# top.net
KiCad netlist of a schematic drawn in Altium Designer
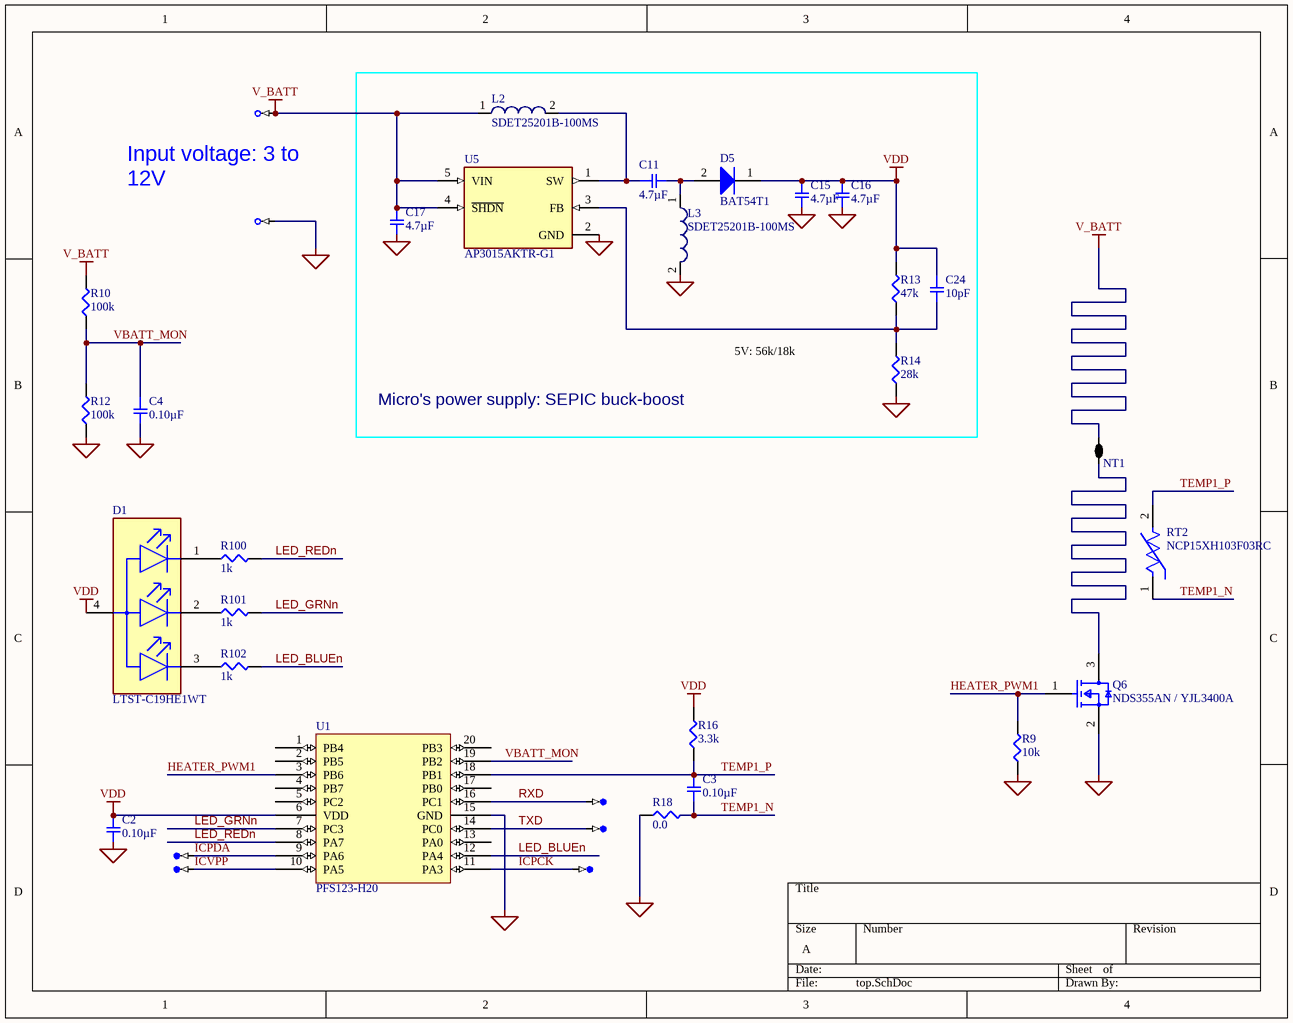
[diagram p0: top.SchDoc]

(export (version "E")
  (design (tool "Eeschema 10.0.6"))
  (components
    (comp (ref "1")
      (value "TP-TH-C-152-H90")
      (footprint "TP-TH-C-152-H90")
      (description "Test Point, Through Hole, Hole Size 0.9 mm, PCB Mount with Silkscreen Box")
      (libsource (lib "TP-TH-C-152-H90-") (part "TP-TH-C-152-H90"))
    )
    (comp (ref "2")
      (value "TP-TH-C-152-H90")
      (footprint "TP-TH-C-152-H90")
      (description "Test Point, Through Hole, Hole Size 0.9 mm, PCB Mount with Silkscreen Box")
      (libsource (lib "TP-TH-C-152-H90-") (part "TP-TH-C-152-H90"))
    )
    (comp (ref "C2")
      (value "0.10µF")
      (footprint "SMD-0402C")
      (description "CAP CER 0.1UF 10V X5R 0402")
      (fields
        (field (name "DIGI-KEY PART NUMBER") "490-10008-1-ND")
        (field (name "PART NUMBER") "GRM152R61A104KE19D")
      )
      (libsource (lib "capacitor_murata_0402") (part "GRM152R61A104KE19D"))
    )
    (comp (ref "C3")
      (value "0.10µF")
      (footprint "SMD-0402C")
      (description "CAP CER 0.1UF 10V X5R 0402")
      (fields
        (field (name "DIGI-KEY PART NUMBER") "490-10008-1-ND")
        (field (name "PART NUMBER") "GRM152R61A104KE19D")
      )
      (libsource (lib "capacitor_murata_0402") (part "GRM152R61A104KE19D"))
    )
    (comp (ref "C4")
      (value "0.10µF")
      (footprint "SMD-0402C")
      (description "CAP CER 0.1UF 10V X5R 0402")
      (fields
        (field (name "DIGI-KEY PART NUMBER") "490-10008-1-ND")
        (field (name "PART NUMBER") "GRM152R61A104KE19D")
      )
      (libsource (lib "capacitor_murata_0402") (part "GRM152R61A104KE19D"))
    )
    (comp (ref "C11")
      (value "4.7µF")
      (footprint "SMD-0603C")
      (description "CAP CER 4.7UF 10V X6S 0603")
      (fields
        (field (name "DIGI-KEY PART NUMBER") "490-10464-1-ND")
        (field (name "PART NUMBER") "GRM185C81A475KE11D")
      )
      (libsource (lib "capacitor_murata_0603") (part "GRM185C81A475KE11D"))
    )
    (comp (ref "C15")
      (value "4.7µF")
      (footprint "SMD-0603C")
      (description "CAP CER 4.7UF 10V X6S 0603")
      (fields
        (field (name "DIGI-KEY PART NUMBER") "490-10464-1-ND")
        (field (name "PART NUMBER") "GRM185C81A475KE11D")
      )
      (libsource (lib "capacitor_murata_0603") (part "GRM185C81A475KE11D"))
    )
    (comp (ref "C16")
      (value "4.7µF")
      (footprint "SMD-0603C")
      (description "CAP CER 4.7UF 10V X6S 0603")
      (fields
        (field (name "DIGI-KEY PART NUMBER") "490-10464-1-ND")
        (field (name "PART NUMBER") "GRM185C81A475KE11D")
      )
      (libsource (lib "capacitor_murata_0603") (part "GRM185C81A475KE11D"))
    )
    (comp (ref "C17")
      (value "4.7µF")
      (footprint "SMD-0603C")
      (description "CAP CER 4.7UF 10V X6S 0603")
      (fields
        (field (name "DIGI-KEY PART NUMBER") "490-10464-1-ND")
        (field (name "PART NUMBER") "GRM185C81A475KE11D")
      )
      (libsource (lib "capacitor_murata_0603") (part "GRM185C81A475KE11D"))
    )
    (comp (ref "C24")
      (value "10pF")
      (footprint "SMD-0402C")
      (description "CAP CER 10PF 50V NP0 0402")
      (fields
        (field (name "DIGI-KEY PART NUMBER") "490-10668-1-ND")
        (field (name "PART NUMBER") "GCM1555C1H100JA16D")
      )
      (libsource (lib "capacitor_murata_0402") (part "GCM1555C1H100JA16D"))
    )
    (comp (ref "D1")
      (value "LTST-C19HE1WT")
      (footprint "FP-LTST-C19HE1WT-MFG")
      (description "LED RGB DIFFUSED CHIP SMD")
      (libsource (lib "Altium Content Vault") (part "2c4e1fdd461916b293eda504ca5a2b6"))
    )
    (comp (ref "D5")
      (value "BAT54T1")
      (footprint "ONSC-SOD-123-2-425-04_V")
      (description "Schottky Barrier Diode, 2-Pin SOD-123, Tape and Reel")
      (fields (field (name "MANUFACTURER") "On Semiconductor"))
      (libsource (lib "Altium Content Vault") (part "ONSC-D-K1A2-2"))
    )
    (comp (ref "L2")
      (value "SDET25201B-100MS")
      (footprint "WE-LQS 252012")
      (description "FIXED IND 10UH 900MA 408MOHM SMD")
      (fields (field (name "MANUFACTURER") "Wuerth Elektronik") (field (name "PARTNUMBER") "74404024100"))
      (libsource (lib "Altium Content Vault") (part "WE-IND-INDUCTOR-2"))
    )
    (comp (ref "L3")
      (value "SDET25201B-100MS")
      (footprint "WE-LQS 252012")
      (description "FIXED IND 10UH 900MA 408MOHM SMD")
      (fields (field (name "MANUFACTURER") "Wuerth Elektronik") (field (name "PARTNUMBER") "74404024100"))
      (libsource (lib "Altium Content Vault") (part "WE-IND-INDUCTOR-2"))
    )
    (comp (ref "NT1")
      (value "2 way net tie junction")
      (footprint "2way_LP")
      (libsource (lib "NetTie") (part "2way"))
    )
    (comp (ref "Q6")
      (value "NDS355AN / YJL3400A")
      (footprint "FP-527AG-01-IPC_C")
      (description "MOSFET N-CH 30V 1.7A SSOT3")
      (fields
        (field (name "OCTOPART") "https://octopart.com/nds355an-on+semiconductor-84330922")
        (field (name "MANUFACTURER PART NUMBER") "NDS355AN")
      )
      (libsource (lib "Altium Content Vault") (part "3b9c635fedb024a5347a57b145af9cc"))
    )
    (comp (ref "R9")
      (value "10k")
      (footprint "SMD-0402-RES")
      (description "RES SMD 10K OHM 5% 1/10W 0402")
      (fields (field (name "PART NUMBER") "ERJ-2GEJ103X") (field (name "DIGI-KEY PART NUMBER") "P10KJCT-ND"))
      (libsource (lib "Panasonic_ERJ_0402") (part "ERJ-2GEJ103X"))
    )
    (comp (ref "R10")
      (value "100k")
      (footprint "SMD-0402-RES")
      (description "RES SMD 100K OHM 5% 1/10W 0402")
      (fields (field (name "PART NUMBER") "ERJ-2GEJ104X") (field (name "DIGI-KEY PART NUMBER") "P100KJCT-ND"))
      (libsource (lib "Panasonic_ERJ_0402") (part "ERJ-2GEJ104X"))
    )
    (comp (ref "R12")
      (value "100k")
      (footprint "SMD-0402-RES")
      (description "RES SMD 100K OHM 5% 1/10W 0402")
      (fields (field (name "PART NUMBER") "ERJ-2GEJ104X") (field (name "DIGI-KEY PART NUMBER") "P100KJCT-ND"))
      (libsource (lib "Panasonic_ERJ_0402") (part "ERJ-2GEJ104X"))
    )
    (comp (ref "R13")
      (value "47k")
      (footprint "SMD-0402-RES")
      (description "RES SMD 10K OHM 5% 1/10W 0402")
      (fields (field (name "PART NUMBER") "ERJ-2GEJ103X") (field (name "DIGI-KEY PART NUMBER") "P10KJCT-ND"))
      (libsource (lib "Panasonic_ERJ_0402") (part "ERJ-2GEJ103X"))
    )
    (comp (ref "R14")
      (value "28k")
      (footprint "SMD-0402-RES")
      (description "RES SMD 10K OHM 5% 1/10W 0402")
      (fields (field (name "PART NUMBER") "ERJ-2GEJ103X") (field (name "DIGI-KEY PART NUMBER") "P10KJCT-ND"))
      (libsource (lib "Panasonic_ERJ_0402") (part "ERJ-2GEJ103X"))
    )
    (comp (ref "R16")
      (value "3.3k")
      (footprint "SMD-0402-RES")
      (description "RES SMD 3.3K OHM 5% 1/10W 0402")
      (fields (field (name "PART NUMBER") "ERJ-2GEJ332X") (field (name "DIGI-KEY PART NUMBER") "P3.3KJCT-ND"))
      (libsource (lib "Panasonic_ERJ_0402") (part "ERJ-2GEJ332X"))
    )
    (comp (ref "R18")
      (value "0.0")
      (footprint "SMD-0402-RES")
      (description "RES SMD 0.0OHM JUMPER 1/10W 0402")
      (fields (field (name "PART NUMBER") "ERJ-2GE0R00X") (field (name "DIGI-KEY PART NUMBER") "P0.0JCT-ND"))
      (libsource (lib "Panasonic_ERJ_0402") (part "ERJ-2GE0R00X"))
    )
    (comp (ref "R100")
      (value "1k")
      (footprint "SMD-0402-RES")
      (description "RES SMD 1K OHM 5% 1/10W 0402")
      (fields (field (name "PART NUMBER") "ERJ-2GEJ102X") (field (name "DIGI-KEY PART NUMBER") "P1.0KJCT-ND"))
      (libsource (lib "Panasonic_ERJ_0402") (part "ERJ-2GEJ102X"))
    )
    (comp (ref "R101")
      (value "1k")
      (footprint "SMD-0402-RES")
      (description "RES SMD 1K OHM 5% 1/10W 0402")
      (fields (field (name "PART NUMBER") "ERJ-2GEJ102X") (field (name "DIGI-KEY PART NUMBER") "P1.0KJCT-ND"))
      (libsource (lib "Panasonic_ERJ_0402") (part "ERJ-2GEJ102X"))
    )
    (comp (ref "R102")
      (value "1k")
      (footprint "SMD-0402-RES")
      (description "RES SMD 1K OHM 5% 1/10W 0402")
      (fields (field (name "PART NUMBER") "ERJ-2GEJ102X") (field (name "DIGI-KEY PART NUMBER") "P1.0KJCT-ND"))
      (libsource (lib "Panasonic_ERJ_0402") (part "ERJ-2GEJ102X"))
    )
    (comp (ref "RT2")
      (value "NCP15XH103F03RC")
      (footprint "FP-NCP15-NCU15-0_05-IPC_C")
      (description "NTC Thermistor for Temperature Sensor, 0402, 10kΩ, 1%, 0.1mA, 5V")
      (fields (field (name "TOLERANCE") "1%"))
      (libsource (lib "Altium Content Vault") (part "3b148a6ebabc5fb4d708a66c052d352"))
    )
    (comp (ref "TP1")
      (value "TP-SM-C-100")
      (footprint "TP-SM-C-100")
      (description "Test Point, Surface Mount, Circular, Pad Diameter 1 mm")
      (fields (field (name "MANUFACTURER") "No Vendor"))
      (libsource (lib "TP-SM-C-100") (part "CMP-0484-00002-2"))
    )
    (comp (ref "TP2")
      (value "TP-SM-C-100")
      (footprint "TP-SM-C-100")
      (description "Test Point, Surface Mount, Circular, Pad Diameter 1 mm")
      (fields (field (name "MANUFACTURER") "No Vendor"))
      (libsource (lib "TP-SM-C-100") (part "CMP-0484-00002-2"))
    )
    (comp (ref "TP3")
      (value "TP-SM-C-100")
      (footprint "TP-SM-C-100")
      (description "Test Point, Surface Mount, Circular, Pad Diameter 1 mm")
      (fields (field (name "MANUFACTURER") "No Vendor"))
      (libsource (lib "TP-SM-C-100") (part "CMP-0484-00002-2"))
    )
    (comp (ref "TP4")
      (value "TP-SM-C-100")
      (footprint "TP-SM-C-100")
      (description "Test Point, Surface Mount, Circular, Pad Diameter 1 mm")
      (fields (field (name "MANUFACTURER") "No Vendor"))
      (libsource (lib "TP-SM-C-100") (part "CMP-0484-00002-2"))
    )
    (comp (ref "TP5")
      (value "TP-SM-C-100")
      (footprint "TP-SM-C-100")
      (description "Test Point, Surface Mount, Circular, Pad Diameter 1 mm")
      (fields (field (name "MANUFACTURER") "No Vendor"))
      (libsource (lib "TP-SM-C-100") (part "CMP-0484-00002-2"))
    )
    (comp (ref "U1")
      (value "PFS123-H20")
      (footprint "TSOP100P600X135-20N")
      (libsource (lib "PFS123") (part "PFS123-H20"))
    )
    (comp (ref "U5")
      (value "AP3015AKTR-G1")
      (footprint "SOT95P280X145-5N")
      (description "Boost Switching Regulator IC Positive Adjustable 1.23V 1 Output 75mA (Switch) SC-74A, SOT-753")
      (fields (field (name "MF") "Diodes Inc."))
      (libsource (lib "AP3015AKTR-G1") (part "AP3015AKTR-G1"))
    )
  )
  (nets
    (net (code "1") (name "/HEATER_PWM1") (class "Default")
      (node (ref "Q6") (pin "1") (pinfunction "G_1") (pintype "passive"))
      (node (ref "R9") (pin "2") (pinfunction "2_2") (pintype "passive"))
      (node (ref "U1") (pin "3") (pinfunction "PB6_3") (pintype "bidirectional"))
    )
    (net (code "2") (name "/ICPCK") (class "Default")
      (node (ref "TP3") (pin "1") (pinfunction "1_1") (pintype "input"))
      (node (ref "U1") (pin "11") (pinfunction "PA3_11") (pintype "bidirectional"))
    )
    (net (code "3") (name "/ICPDA") (class "Default")
      (node (ref "TP1") (pin "1") (pinfunction "1_1") (pintype "input"))
      (node (ref "U1") (pin "9") (pinfunction "PA6_9") (pintype "bidirectional"))
    )
    (net (code "4") (name "/ICVPP") (class "Default")
      (node (ref "TP2") (pin "1") (pinfunction "1_1") (pintype "input"))
      (node (ref "U1") (pin "10") (pinfunction "PA5_10") (pintype "bidirectional"))
    )
    (net (code "5") (name "/LED_BLUEn") (class "Default")
      (node (ref "R102") (pin "2") (pinfunction "2_2") (pintype "passive"))
      (node (ref "U1") (pin "12") (pinfunction "PA4_12") (pintype "bidirectional"))
    )
    (net (code "6") (name "/LED_GRNn") (class "Default")
      (node (ref "R101") (pin "2") (pinfunction "2_2") (pintype "passive"))
      (node (ref "U1") (pin "7") (pinfunction "PC3_7") (pintype "bidirectional"))
    )
    (net (code "7") (name "/LED_REDn") (class "Default")
      (node (ref "R100") (pin "2") (pinfunction "2_2") (pintype "passive"))
      (node (ref "U1") (pin "8") (pinfunction "PA7_8") (pintype "bidirectional"))
    )
    (net (code "8") (name "/RXD") (class "Default")
      (node (ref "TP4") (pin "1") (pinfunction "1_1") (pintype "input"))
      (node (ref "U1") (pin "16") (pinfunction "PC1_16") (pintype "bidirectional"))
    )
    (net (code "9") (name "/TEMP1_N") (class "Default")
      (node (ref "C3") (pin "2") (pinfunction "2_2") (pintype "passive"))
      (node (ref "R18") (pin "2") (pinfunction "2_2") (pintype "passive"))
      (node (ref "RT2") (pin "1") (pinfunction "1_1") (pintype "passive"))
    )
    (net (code "10") (name "/TEMP1_P") (class "Default")
      (node (ref "C3") (pin "1") (pinfunction "1_1") (pintype "passive"))
      (node (ref "R16") (pin "1") (pinfunction "1_1") (pintype "passive"))
      (node (ref "RT2") (pin "2") (pinfunction "2_2") (pintype "passive"))
      (node (ref "U1") (pin "18") (pinfunction "PB1_18") (pintype "bidirectional"))
    )
    (net (code "11") (name "/TXD") (class "Default")
      (node (ref "TP5") (pin "1") (pinfunction "1_1") (pintype "input"))
      (node (ref "U1") (pin "14") (pinfunction "PC0_14") (pintype "bidirectional"))
    )
    (net (code "12") (name "/VBATT_MON") (class "Default")
      (node (ref "C4") (pin "1") (pinfunction "1_1") (pintype "passive"))
      (node (ref "R10") (pin "1") (pinfunction "1_1") (pintype "passive"))
      (node (ref "R12") (pin "2") (pinfunction "2_2") (pintype "passive"))
      (node (ref "U1") (pin "19") (pinfunction "PB2_19") (pintype "bidirectional"))
    )
    (net (code "13") (name "GND") (class "Default")
      (node (ref "2") (pin "1") (pinfunction "1_1") (pintype "input"))
      (node (ref "C15") (pin "2") (pinfunction "2_2") (pintype "passive"))
      (node (ref "C16") (pin "2") (pinfunction "2_2") (pintype "passive"))
      (node (ref "C17") (pin "2") (pinfunction "2_2") (pintype "passive"))
      (node (ref "C2") (pin "2") (pinfunction "2_2") (pintype "passive"))
      (node (ref "C4") (pin "2") (pinfunction "2_2") (pintype "passive"))
      (node (ref "L3") (pin "2") (pinfunction "2_2") (pintype "passive"))
      (node (ref "Q6") (pin "2") (pinfunction "S_2") (pintype "passive"))
      (node (ref "R12") (pin "1") (pinfunction "1_1") (pintype "passive"))
      (node (ref "R14") (pin "1") (pinfunction "1_1") (pintype "passive"))
      (node (ref "R18") (pin "1") (pinfunction "1_1") (pintype "passive"))
      (node (ref "R9") (pin "1") (pinfunction "1_1") (pintype "passive"))
      (node (ref "U1") (pin "15") (pinfunction "GND_15") (pintype "power_in"))
      (node (ref "U5") (pin "2") (pinfunction "GND_2") (pintype "power_in"))
    )
    (net (code "14") (name "Net-(D1-BLUE_C)") (class "Default")
      (node (ref "D1") (pin "3") (pinfunction "BLUE_C_3") (pintype "passive"))
      (node (ref "R102") (pin "1") (pinfunction "1_1") (pintype "passive"))
    )
    (net (code "15") (name "Net-(D1-GREEN_C)") (class "Default")
      (node (ref "D1") (pin "2") (pinfunction "GREEN_C_2") (pintype "passive"))
      (node (ref "R101") (pin "1") (pinfunction "1_1") (pintype "passive"))
    )
    (net (code "16") (name "Net-(D1-RED_C)") (class "Default")
      (node (ref "D1") (pin "1") (pinfunction "RED_C_1") (pintype "passive"))
      (node (ref "R100") (pin "1") (pinfunction "1_1") (pintype "passive"))
    )
    (net (code "17") (name "Net-(D5-A)") (class "Default")
      (node (ref "C11") (pin "2") (pinfunction "2_2") (pintype "passive"))
      (node (ref "D5") (pin "2") (pinfunction "A_2") (pintype "passive"))
      (node (ref "L3") (pin "1") (pinfunction "1_1") (pintype "passive"))
    )
    (net (code "18") (name "Net-(Q6-D)") (class "Default")
      (node (ref "NT1") (pin "2") (pinfunction "2_2") (pintype "passive"))
      (node (ref "Q6") (pin "3") (pinfunction "D_3") (pintype "passive"))
    )
    (net (code "19") (name "Net-(U5-FB)") (class "Default")
      (node (ref "C24") (pin "2") (pinfunction "2_2") (pintype "passive"))
      (node (ref "R13") (pin "1") (pinfunction "1_1") (pintype "passive"))
      (node (ref "R14") (pin "2") (pinfunction "2_2") (pintype "passive"))
      (node (ref "U5") (pin "3") (pinfunction "FB_3") (pintype "input"))
    )
    (net (code "20") (name "Net-(U5-SW)") (class "Default")
      (node (ref "C11") (pin "1") (pinfunction "1_1") (pintype "passive"))
      (node (ref "L2") (pin "2") (pinfunction "2_2") (pintype "passive"))
      (node (ref "U5") (pin "1") (pinfunction "SW_1") (pintype "output"))
    )
    (net (code "21") (name "VDD") (class "Default")
      (node (ref "C15") (pin "1") (pinfunction "1_1") (pintype "passive"))
      (node (ref "C16") (pin "1") (pinfunction "1_1") (pintype "passive"))
      (node (ref "C2") (pin "1") (pinfunction "1_1") (pintype "passive"))
      (node (ref "C24") (pin "1") (pinfunction "1_1") (pintype "passive"))
      (node (ref "D1") (pin "4") (pinfunction "A_4") (pintype "passive"))
      (node (ref "D5") (pin "1") (pinfunction "K_1") (pintype "passive"))
      (node (ref "R13") (pin "2") (pinfunction "2_2") (pintype "passive"))
      (node (ref "R16") (pin "2") (pinfunction "2_2") (pintype "passive"))
      (node (ref "U1") (pin "6") (pinfunction "VDD_6") (pintype "power_in"))
    )
    (net (code "22") (name "V_BATT") (class "Default")
      (node (ref "1") (pin "1") (pinfunction "1_1") (pintype "input"))
      (node (ref "C17") (pin "1") (pinfunction "1_1") (pintype "passive"))
      (node (ref "L2") (pin "1") (pinfunction "1_1") (pintype "passive"))
      (node (ref "NT1") (pin "1") (pinfunction "1_1") (pintype "passive"))
      (node (ref "R10") (pin "2") (pinfunction "2_2") (pintype "passive"))
      (node (ref "U5") (pin "4") (pinfunction "~{SHDN}_4") (pintype "input"))
      (node (ref "U5") (pin "5") (pinfunction "VIN_5") (pintype "input"))
    )
    (net (code "23") (name "unconnected-(U1-PA0-Pad13)") (class "Default")
      (node (ref "U1") (pin "13") (pinfunction "PA0_13") (pintype "bidirectional"))
    )
    (net (code "24") (name "unconnected-(U1-PB0-Pad17)") (class "Default")
      (node (ref "U1") (pin "17") (pinfunction "PB0_17") (pintype "bidirectional"))
    )
    (net (code "25") (name "unconnected-(U1-PB3-Pad20)") (class "Default")
      (node (ref "U1") (pin "20") (pinfunction "PB3_20") (pintype "bidirectional"))
    )
    (net (code "26") (name "unconnected-(U1-PB4-Pad1)") (class "Default")
      (node (ref "U1") (pin "1") (pinfunction "PB4_1") (pintype "bidirectional"))
    )
    (net (code "27") (name "unconnected-(U1-PB5-Pad2)") (class "Default")
      (node (ref "U1") (pin "2") (pinfunction "PB5_2") (pintype "bidirectional"))
    )
    (net (code "28") (name "unconnected-(U1-PB7-Pad4)") (class "Default")
      (node (ref "U1") (pin "4") (pinfunction "PB7_4") (pintype "bidirectional"))
    )
    (net (code "29") (name "unconnected-(U1-PC2-Pad5)") (class "Default")
      (node (ref "U1") (pin "5") (pinfunction "PC2_5") (pintype "bidirectional"))
    )
  )
)
